# mega-shield.net
KiCad netlist of a schematic drawn in EAGLE
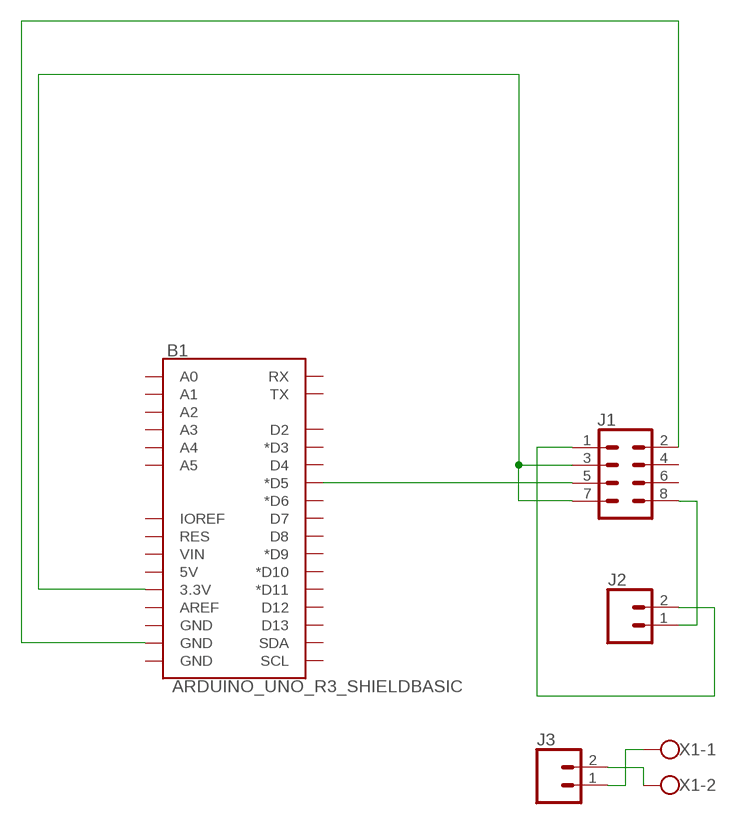
[diagram p0: schematic, sheet 1]

(export (version "E")
  (design (tool "Eeschema 10.0.6"))
  (components
    (comp (ref "B1")
      (value "ARDUINO_UNO_R3_SHIELDBASIC")
      (footprint "eagle-import:UNO_R3_SHIELD")
      (libsource (lib "eagle-import") (part "ARDUINO_UNO_R3_SHIELDBASIC"))
    )
    (comp (ref "J1")
      (value "CONN_04X2")
      (footprint "eagle-import:2X4")
      (libsource (lib "eagle-import") (part "CONN_04X2"))
    )
    (comp (ref "J2")
      (value "CONN_02")
      (footprint "eagle-import:1X02")
      (libsource (lib "eagle-import") (part "CONN_02"))
    )
    (comp (ref "J3")
      (value "CONN_02")
      (footprint "eagle-import:1X02")
      (libsource (lib "eagle-import") (part "CONN_02"))
    )
    (comp (ref "X1")
      (value "W237-102")
      (footprint "eagle-import:W237-102")
      (fields (field (name "MPN") "237-102"))
      (libsource (lib "eagle-import") (part "W237-102"))
    )
  )
  (nets
    (net (code "1") (name "Net-(B1-*D5)") (class "Default")
      (node (ref "B1") (pin "D5") (pinfunction "*D5_D5") (pintype "bidirectional"))
      (node (ref "J1") (pin "5") (pinfunction "5_5") (pintype "passive"))
    )
    (net (code "2") (name "Net-(B1-GND-PadGND@1)") (class "Default")
      (node (ref "B1") (pin "GND@1") (pinfunction "GND_GND@1") (pintype "bidirectional"))
      (node (ref "J1") (pin "2") (pinfunction "2_2") (pintype "passive"))
    )
    (net (code "3") (name "Net-(B1-Pad3.3V)") (class "Default")
      (node (ref "B1") (pin "3.3V") (pinfunction "3.3V_3.3V") (pintype "bidirectional"))
      (node (ref "J1") (pin "3") (pinfunction "3_3") (pintype "passive"))
      (node (ref "J1") (pin "7") (pinfunction "7_7") (pintype "passive"))
    )
    (net (code "4") (name "Net-(J1-Pad1)") (class "Default")
      (node (ref "J1") (pin "1") (pinfunction "1_1") (pintype "passive"))
      (node (ref "J2") (pin "2") (pinfunction "2_2") (pintype "passive"))
    )
    (net (code "5") (name "Net-(J1-Pad8)") (class "Default")
      (node (ref "J1") (pin "8") (pinfunction "8_8") (pintype "passive"))
      (node (ref "J2") (pin "1") (pinfunction "1_1") (pintype "passive"))
    )
    (net (code "6") (name "Net-(X1A-KL)") (class "Default")
      (node (ref "J3") (pin "1") (pinfunction "1_1") (pintype "passive"))
      (node (ref "X1") (pin "1") (pinfunction "KL_1") (pintype "passive"))
    )
    (net (code "7") (name "Net-(X1B-KL)") (class "Default")
      (node (ref "J3") (pin "2") (pinfunction "2_2") (pintype "passive"))
      (node (ref "X1") (pin "2") (pinfunction "KL_2") (pintype "passive"))
    )
    (net (code "8") (name "unconnected-(B1-*D3-PadD3)") (class "Default")
      (node (ref "B1") (pin "D3") (pinfunction "*D3_D3") (pintype "bidirectional"))
    )
    (net (code "9") (name "unconnected-(B1-*D6-PadD6)") (class "Default")
      (node (ref "B1") (pin "D6") (pinfunction "*D6_D6") (pintype "bidirectional"))
    )
    (net (code "10") (name "unconnected-(B1-*D9-PadD9)") (class "Default")
      (node (ref "B1") (pin "D9") (pinfunction "*D9_D9") (pintype "bidirectional"))
    )
    (net (code "11") (name "unconnected-(B1-*D10-PadD10)") (class "Default")
      (node (ref "B1") (pin "D10") (pinfunction "*D10_D10") (pintype "bidirectional"))
    )
    (net (code "12") (name "unconnected-(B1-*D11-PadD11)") (class "Default")
      (node (ref "B1") (pin "D11") (pinfunction "*D11_D11") (pintype "bidirectional"))
    )
    (net (code "13") (name "unconnected-(B1-GND-PadGND@0)") (class "Default")
      (node (ref "B1") (pin "GND@0") (pinfunction "GND_GND@0") (pintype "bidirectional"))
    )
    (net (code "14") (name "unconnected-(B1-GND-PadGND@2)") (class "Default")
      (node (ref "B1") (pin "GND@2") (pinfunction "GND_GND@2") (pintype "bidirectional"))
    )
    (net (code "15") (name "unconnected-(B1-Pad5V)") (class "Default")
      (node (ref "B1") (pin "5V") (pinfunction "5V_5V") (pintype "bidirectional"))
    )
    (net (code "16") (name "unconnected-(B1-PadA0)") (class "Default")
      (node (ref "B1") (pin "A0") (pinfunction "A0_A0") (pintype "bidirectional"))
    )
    (net (code "17") (name "unconnected-(B1-PadA1)") (class "Default")
      (node (ref "B1") (pin "A1") (pinfunction "A1_A1") (pintype "bidirectional"))
    )
    (net (code "18") (name "unconnected-(B1-PadA2)") (class "Default")
      (node (ref "B1") (pin "A2") (pinfunction "A2_A2") (pintype "bidirectional"))
    )
    (net (code "19") (name "unconnected-(B1-PadA3)") (class "Default")
      (node (ref "B1") (pin "A3") (pinfunction "A3_A3") (pintype "bidirectional"))
    )
    (net (code "20") (name "unconnected-(B1-PadA4)") (class "Default")
      (node (ref "B1") (pin "A4") (pinfunction "A4_A4") (pintype "bidirectional"))
    )
    (net (code "21") (name "unconnected-(B1-PadA5)") (class "Default")
      (node (ref "B1") (pin "A5") (pinfunction "A5_A5") (pintype "bidirectional"))
    )
    (net (code "22") (name "unconnected-(B1-PadAREF)") (class "Default")
      (node (ref "B1") (pin "AREF") (pinfunction "AREF_AREF") (pintype "bidirectional"))
    )
    (net (code "23") (name "unconnected-(B1-PadD2)") (class "Default")
      (node (ref "B1") (pin "D2") (pinfunction "D2_D2") (pintype "bidirectional"))
    )
    (net (code "24") (name "unconnected-(B1-PadD4)") (class "Default")
      (node (ref "B1") (pin "D4") (pinfunction "D4_D4") (pintype "bidirectional"))
    )
    (net (code "25") (name "unconnected-(B1-PadD7)") (class "Default")
      (node (ref "B1") (pin "D7") (pinfunction "D7_D7") (pintype "bidirectional"))
    )
    (net (code "26") (name "unconnected-(B1-PadD8)") (class "Default")
      (node (ref "B1") (pin "D8") (pinfunction "D8_D8") (pintype "bidirectional"))
    )
    (net (code "27") (name "unconnected-(B1-PadD12)") (class "Default")
      (node (ref "B1") (pin "D12") (pinfunction "D12_D12") (pintype "bidirectional"))
    )
    (net (code "28") (name "unconnected-(B1-PadD13)") (class "Default")
      (node (ref "B1") (pin "D13") (pinfunction "D13_D13") (pintype "bidirectional"))
    )
    (net (code "29") (name "unconnected-(B1-PadIOREF)") (class "Default")
      (node (ref "B1") (pin "IOREF") (pinfunction "IOREF_IOREF") (pintype "bidirectional"))
    )
    (net (code "30") (name "unconnected-(B1-PadRES)") (class "Default")
      (node (ref "B1") (pin "RES") (pinfunction "RES_RES") (pintype "bidirectional"))
    )
    (net (code "31") (name "unconnected-(B1-PadRX)") (class "Default")
      (node (ref "B1") (pin "RX") (pinfunction "RX_RX") (pintype "bidirectional"))
    )
    (net (code "32") (name "unconnected-(B1-PadSCL)") (class "Default")
      (node (ref "B1") (pin "SCL") (pinfunction "SCL_SCL") (pintype "bidirectional"))
    )
    (net (code "33") (name "unconnected-(B1-PadSDA)") (class "Default")
      (node (ref "B1") (pin "SDA") (pinfunction "SDA_SDA") (pintype "bidirectional"))
    )
    (net (code "34") (name "unconnected-(B1-PadTX)") (class "Default")
      (node (ref "B1") (pin "TX") (pinfunction "TX_TX") (pintype "bidirectional"))
    )
    (net (code "35") (name "unconnected-(B1-PadVIN)") (class "Default")
      (node (ref "B1") (pin "VIN") (pinfunction "VIN_VIN") (pintype "bidirectional"))
    )
    (net (code "36") (name "unconnected-(J1-Pad4)") (class "Default")
      (node (ref "J1") (pin "4") (pinfunction "4_4") (pintype "passive"))
    )
    (net (code "37") (name "unconnected-(J1-Pad6)") (class "Default")
      (node (ref "J1") (pin "6") (pinfunction "6_6") (pintype "passive"))
    )
  )
)
